# tiny_rack_v2_psu_exp_170.net
KiCad netlist of a schematic drawn in EAGLE
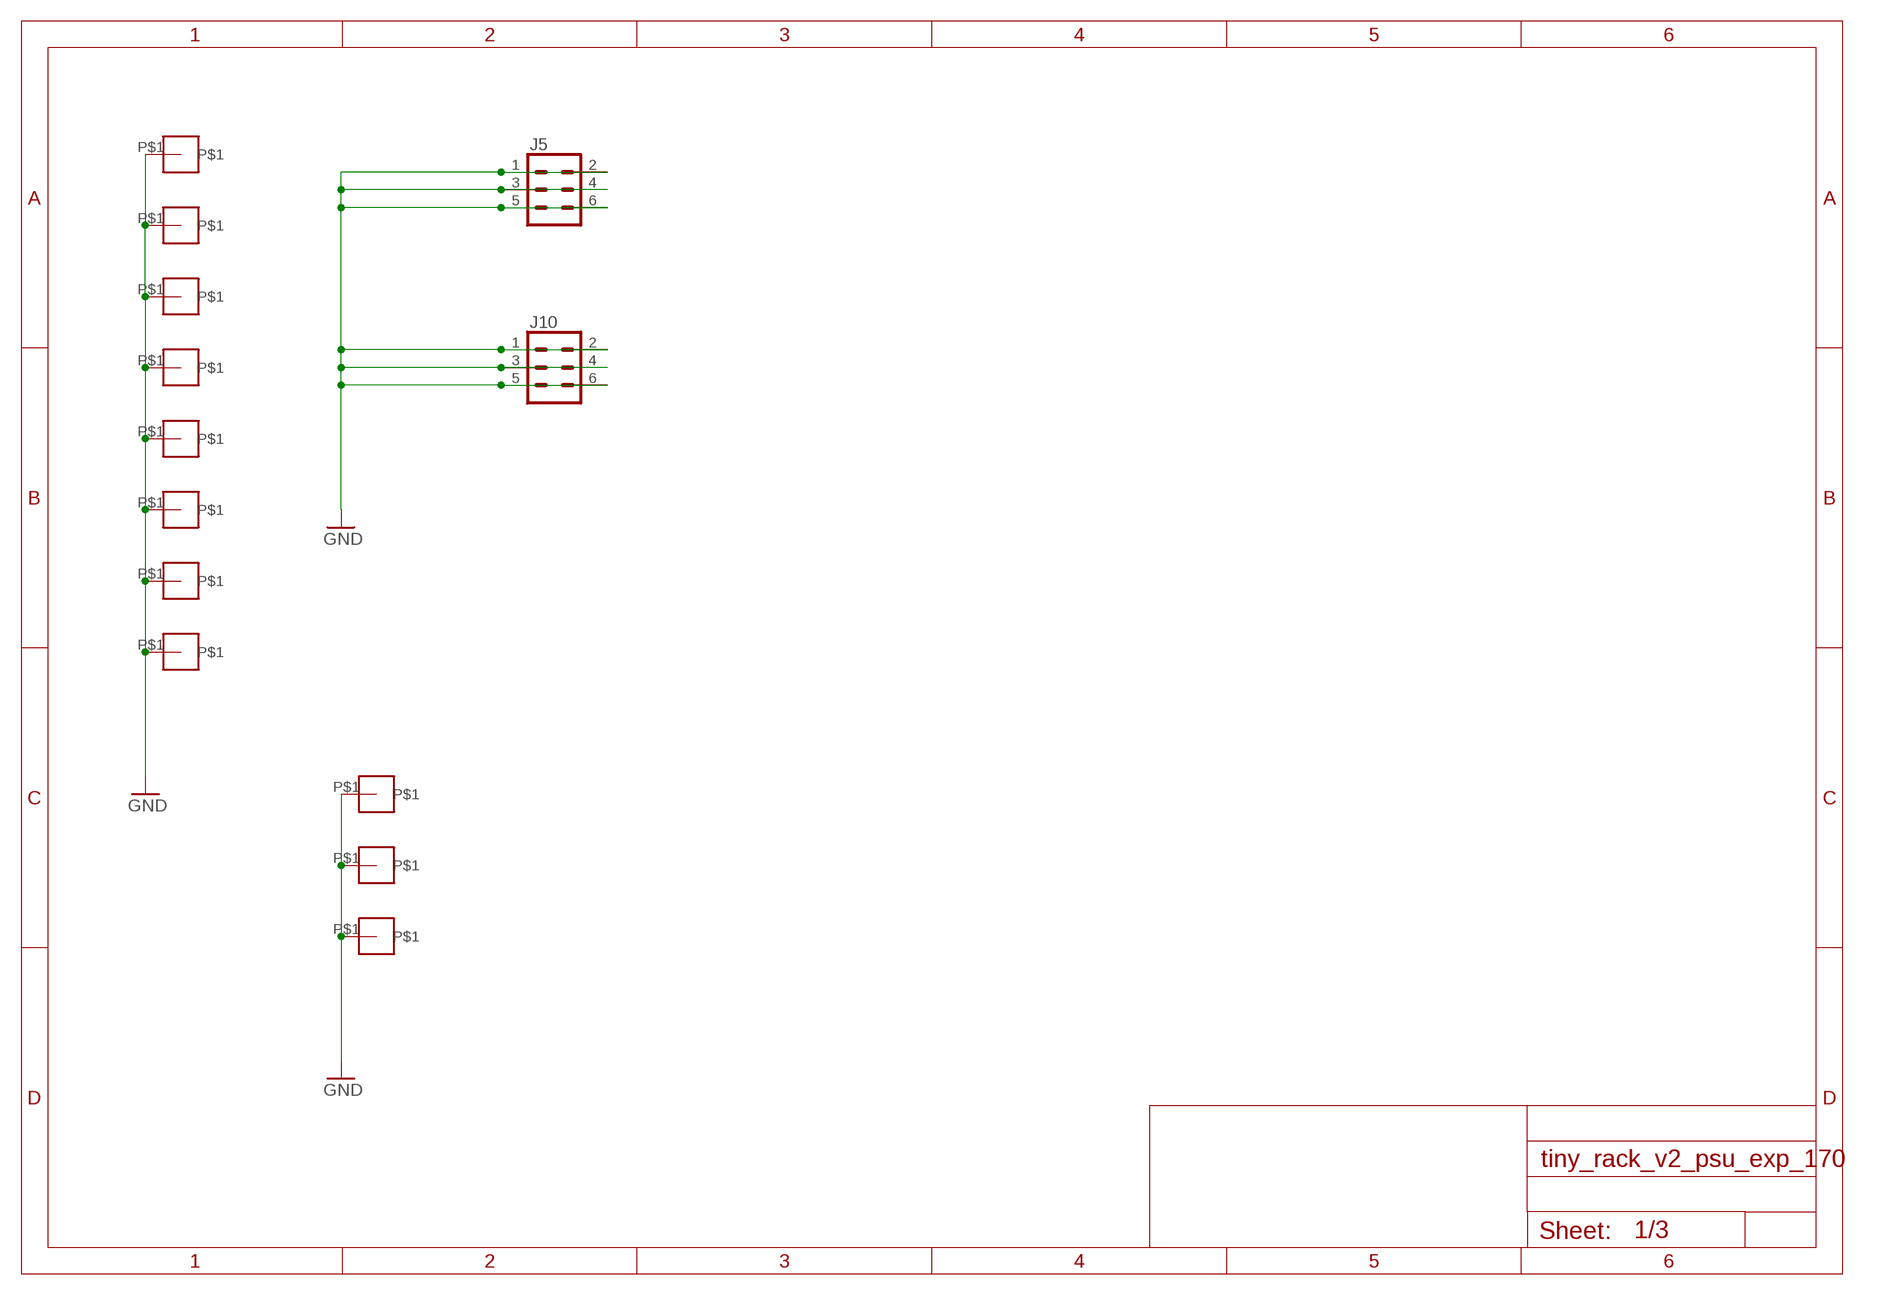
[diagram p0: schematic, sheet 1]
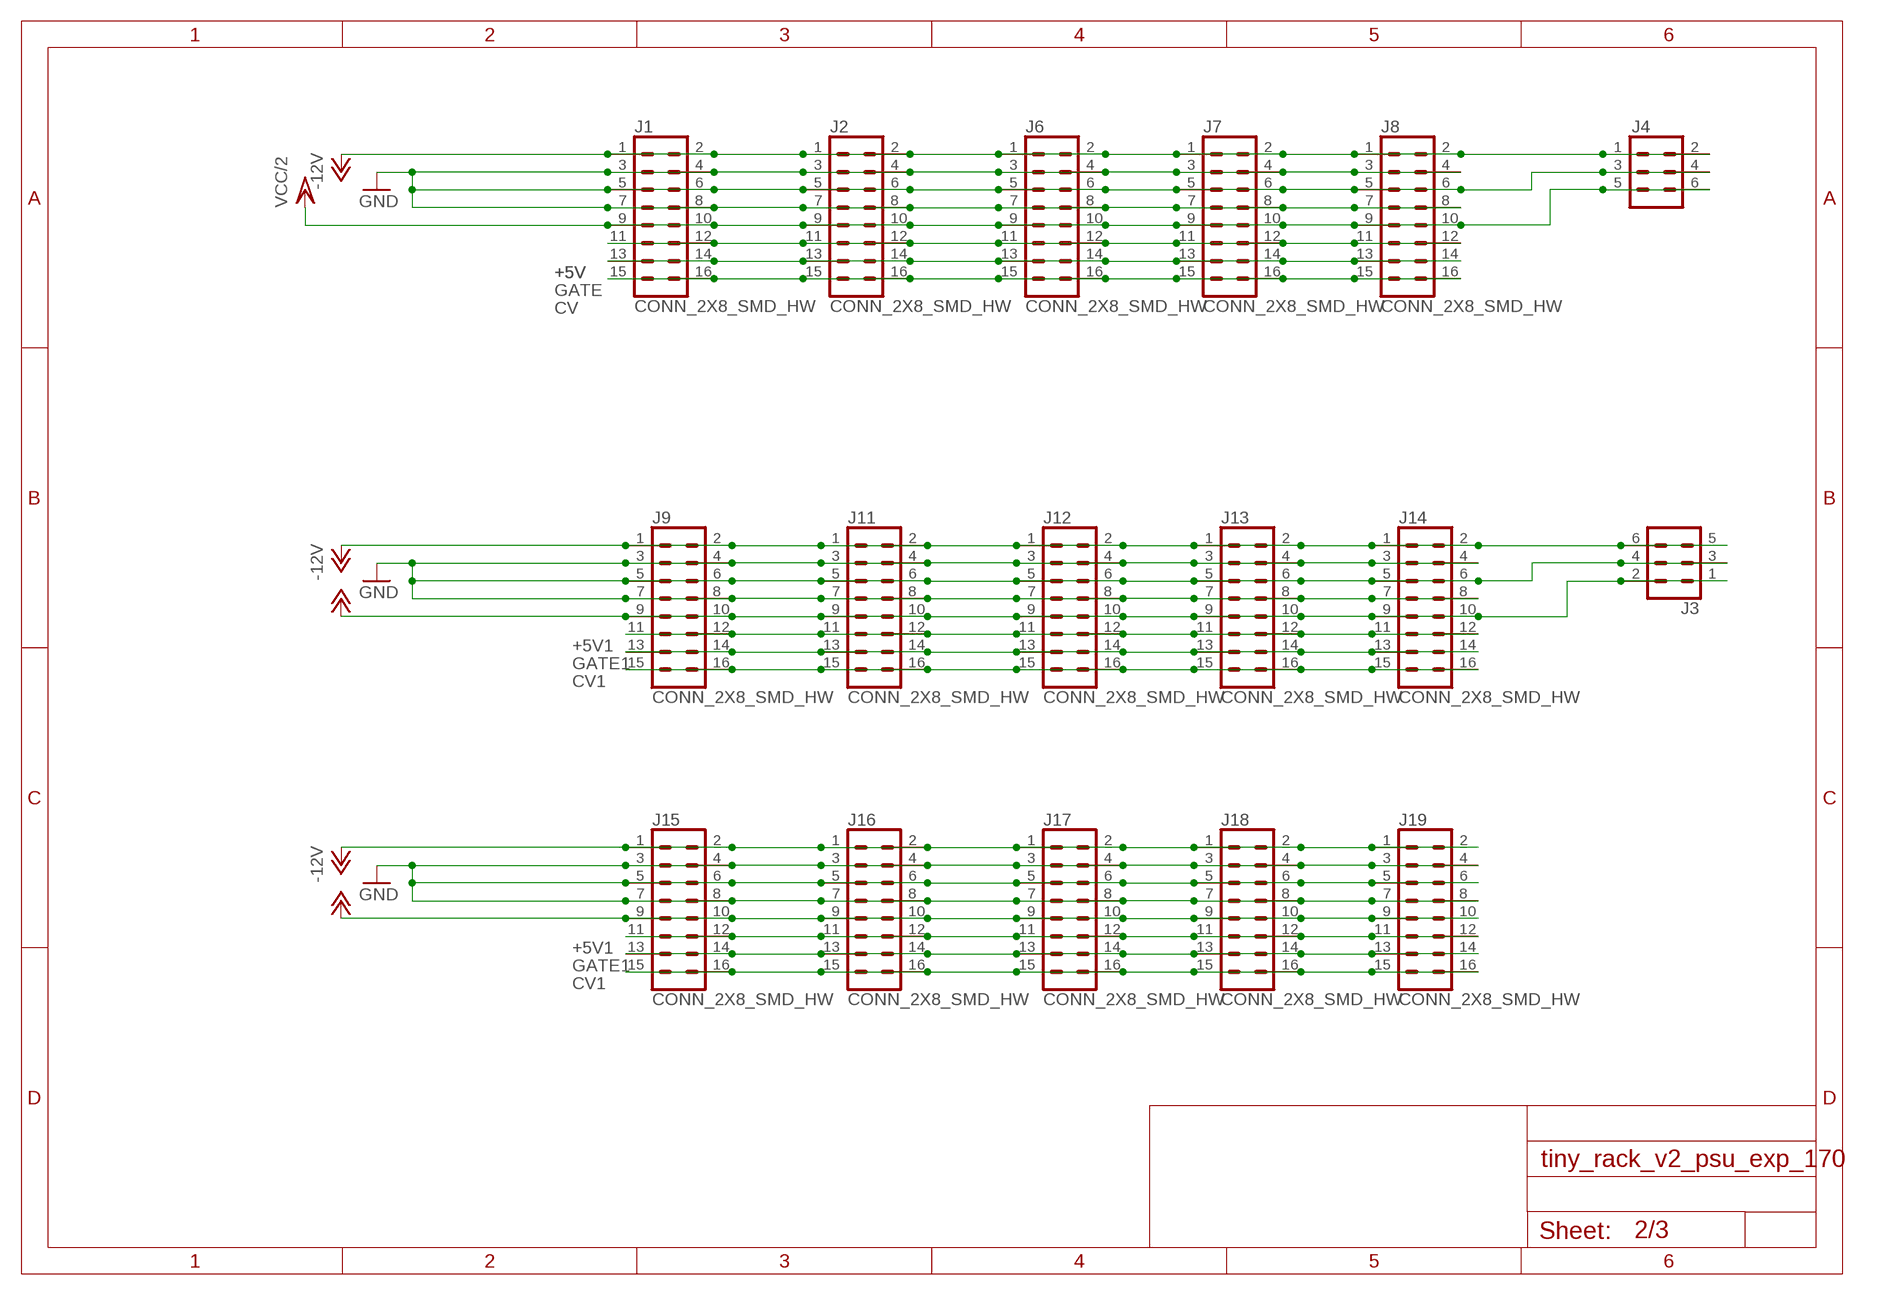
[diagram p1: schematic, sheet 2]
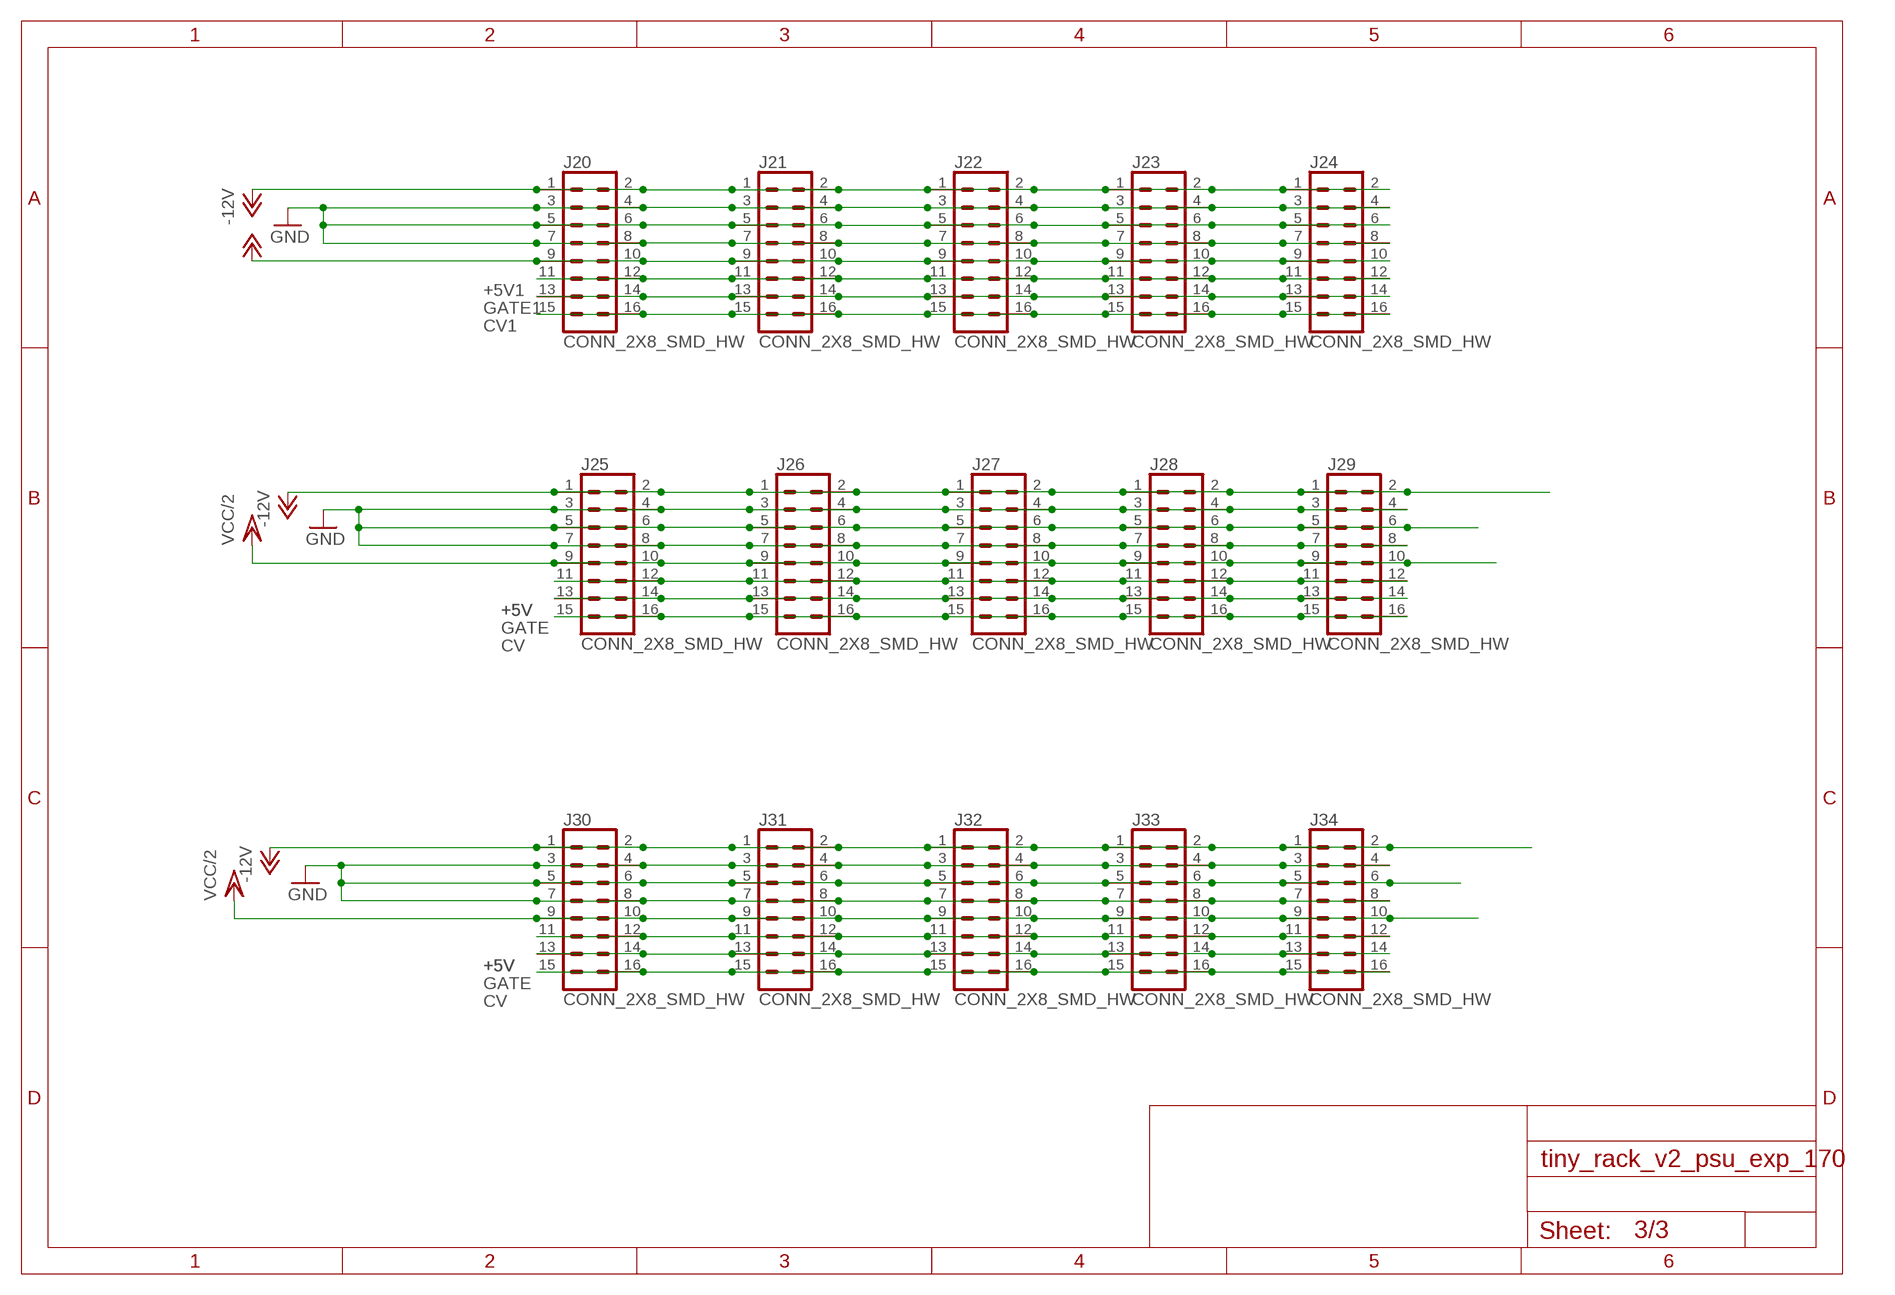
[diagram p2: schematic, sheet 3]

(export (version "E")
  (design (tool "Eeschema 10.0.6"))
  (components
    (comp (ref "J5")
      (value "CONN_03X2FEMALE_SMD")
      (footprint "eagle-import:2X3_SMD")
      (libsource (lib "eagle-import") (part "CONN_03X2FEMALE_SMD"))
    )
    (comp (ref "J10")
      (value "CONN_03X2FEMALE_SMD")
      (footprint "eagle-import:2X3_SMD")
      (libsource (lib "eagle-import") (part "CONN_03X2FEMALE_SMD"))
    )
    (comp (ref "U$1")
      (value "M3-HOLE")
      (footprint "eagle-import:M3-HOLE")
      (libsource (lib "eagle-import") (part "M3-HOLE"))
    )
    (comp (ref "U$2")
      (value "M3-HOLE")
      (footprint "eagle-import:M3-HOLE")
      (libsource (lib "eagle-import") (part "M3-HOLE"))
    )
    (comp (ref "U$3")
      (value "M3-HOLE")
      (footprint "eagle-import:M3-HOLE")
      (libsource (lib "eagle-import") (part "M3-HOLE"))
    )
    (comp (ref "U$4")
      (value "M3-HOLE")
      (footprint "eagle-import:M3-HOLE")
      (libsource (lib "eagle-import") (part "M3-HOLE"))
    )
    (comp (ref "U$5")
      (value "M3-HOLE")
      (footprint "eagle-import:M3-HOLE")
      (libsource (lib "eagle-import") (part "M3-HOLE"))
    )
    (comp (ref "U$6")
      (value "M3-HOLE")
      (footprint "eagle-import:M3-HOLE")
      (libsource (lib "eagle-import") (part "M3-HOLE"))
    )
    (comp (ref "U$8")
      (value "M3-HOLE")
      (footprint "eagle-import:M3-HOLE")
      (libsource (lib "eagle-import") (part "M3-HOLE"))
    )
    (comp (ref "U$9")
      (value "M3-HOLE")
      (footprint "eagle-import:M3-HOLE")
      (libsource (lib "eagle-import") (part "M3-HOLE"))
    )
    (comp (ref "U$10")
      (value "M3-HOLE")
      (footprint "eagle-import:M3-HOLE")
      (libsource (lib "eagle-import") (part "M3-HOLE"))
    )
    (comp (ref "U$11")
      (value "M3-HOLE")
      (footprint "eagle-import:M3-HOLE")
      (libsource (lib "eagle-import") (part "M3-HOLE"))
    )
    (comp (ref "U$12")
      (value "M3-HOLE")
      (footprint "eagle-import:M3-HOLE")
      (libsource (lib "eagle-import") (part "M3-HOLE"))
    )
    (comp (ref "J20")
      (value "CONN_2X8_SMD_HW")
      (footprint "eagle-import:2X8-SHROUDED_SMD_HW")
      (libsource (lib "eagle-import") (part "CONN_2X8_SMD_HW"))
    )
    (comp (ref "J21")
      (value "CONN_2X8_SMD_HW")
      (footprint "eagle-import:2X8-SHROUDED_SMD_HW")
      (libsource (lib "eagle-import") (part "CONN_2X8_SMD_HW"))
    )
    (comp (ref "J22")
      (value "CONN_2X8_SMD_HW")
      (footprint "eagle-import:2X8-SHROUDED_SMD_HW")
      (libsource (lib "eagle-import") (part "CONN_2X8_SMD_HW"))
    )
    (comp (ref "J23")
      (value "CONN_2X8_SMD_HW")
      (footprint "eagle-import:2X8-SHROUDED_SMD_HW")
      (libsource (lib "eagle-import") (part "CONN_2X8_SMD_HW"))
    )
    (comp (ref "J24")
      (value "CONN_2X8_SMD_HW")
      (footprint "eagle-import:2X8-SHROUDED_SMD_HW")
      (libsource (lib "eagle-import") (part "CONN_2X8_SMD_HW"))
    )
    (comp (ref "J25")
      (value "CONN_2X8_SMD_HW")
      (footprint "eagle-import:2X8-SHROUDED_SMD_HW")
      (libsource (lib "eagle-import") (part "CONN_2X8_SMD_HW"))
    )
    (comp (ref "J26")
      (value "CONN_2X8_SMD_HW")
      (footprint "eagle-import:2X8-SHROUDED_SMD_HW")
      (libsource (lib "eagle-import") (part "CONN_2X8_SMD_HW"))
    )
    (comp (ref "J27")
      (value "CONN_2X8_SMD_HW")
      (footprint "eagle-import:2X8-SHROUDED_SMD_HW")
      (libsource (lib "eagle-import") (part "CONN_2X8_SMD_HW"))
    )
    (comp (ref "J28")
      (value "CONN_2X8_SMD_HW")
      (footprint "eagle-import:2X8-SHROUDED_SMD_HW")
      (libsource (lib "eagle-import") (part "CONN_2X8_SMD_HW"))
    )
    (comp (ref "J29")
      (value "CONN_2X8_SMD_HW")
      (footprint "eagle-import:2X8-SHROUDED_SMD_HW")
      (libsource (lib "eagle-import") (part "CONN_2X8_SMD_HW"))
    )
    (comp (ref "J30")
      (value "CONN_2X8_SMD_HW")
      (footprint "eagle-import:2X8-SHROUDED_SMD_HW")
      (libsource (lib "eagle-import") (part "CONN_2X8_SMD_HW"))
    )
    (comp (ref "J31")
      (value "CONN_2X8_SMD_HW")
      (footprint "eagle-import:2X8-SHROUDED_SMD_HW")
      (libsource (lib "eagle-import") (part "CONN_2X8_SMD_HW"))
    )
    (comp (ref "J32")
      (value "CONN_2X8_SMD_HW")
      (footprint "eagle-import:2X8-SHROUDED_SMD_HW")
      (libsource (lib "eagle-import") (part "CONN_2X8_SMD_HW"))
    )
    (comp (ref "J33")
      (value "CONN_2X8_SMD_HW")
      (footprint "eagle-import:2X8-SHROUDED_SMD_HW")
      (libsource (lib "eagle-import") (part "CONN_2X8_SMD_HW"))
    )
    (comp (ref "J34")
      (value "CONN_2X8_SMD_HW")
      (footprint "eagle-import:2X8-SHROUDED_SMD_HW")
      (libsource (lib "eagle-import") (part "CONN_2X8_SMD_HW"))
    )
    (comp (ref "J1")
      (value "CONN_2X8_SMD_HW")
      (footprint "eagle-import:2X8-SHROUDED_SMD_HW")
      (libsource (lib "eagle-import") (part "CONN_2X8_SMD_HW"))
    )
    (comp (ref "J2")
      (value "CONN_2X8_SMD_HW")
      (footprint "eagle-import:2X8-SHROUDED_SMD_HW")
      (libsource (lib "eagle-import") (part "CONN_2X8_SMD_HW"))
    )
    (comp (ref "J3")
      (value "CONN_03X2FEMALE_SMD")
      (footprint "eagle-import:2X3_SMD")
      (libsource (lib "eagle-import") (part "CONN_03X2FEMALE_SMD"))
    )
    (comp (ref "J4")
      (value "CONN_03X2FEMALE_SMD")
      (footprint "eagle-import:2X3_SMD")
      (libsource (lib "eagle-import") (part "CONN_03X2FEMALE_SMD"))
    )
    (comp (ref "J6")
      (value "CONN_2X8_SMD_HW")
      (footprint "eagle-import:2X8-SHROUDED_SMD_HW")
      (libsource (lib "eagle-import") (part "CONN_2X8_SMD_HW"))
    )
    (comp (ref "J7")
      (value "CONN_2X8_SMD_HW")
      (footprint "eagle-import:2X8-SHROUDED_SMD_HW")
      (libsource (lib "eagle-import") (part "CONN_2X8_SMD_HW"))
    )
    (comp (ref "J8")
      (value "CONN_2X8_SMD_HW")
      (footprint "eagle-import:2X8-SHROUDED_SMD_HW")
      (libsource (lib "eagle-import") (part "CONN_2X8_SMD_HW"))
    )
    (comp (ref "J9")
      (value "CONN_2X8_SMD_HW")
      (footprint "eagle-import:2X8-SHROUDED_SMD_HW")
      (libsource (lib "eagle-import") (part "CONN_2X8_SMD_HW"))
    )
    (comp (ref "J11")
      (value "CONN_2X8_SMD_HW")
      (footprint "eagle-import:2X8-SHROUDED_SMD_HW")
      (libsource (lib "eagle-import") (part "CONN_2X8_SMD_HW"))
    )
    (comp (ref "J12")
      (value "CONN_2X8_SMD_HW")
      (footprint "eagle-import:2X8-SHROUDED_SMD_HW")
      (libsource (lib "eagle-import") (part "CONN_2X8_SMD_HW"))
    )
    (comp (ref "J13")
      (value "CONN_2X8_SMD_HW")
      (footprint "eagle-import:2X8-SHROUDED_SMD_HW")
      (libsource (lib "eagle-import") (part "CONN_2X8_SMD_HW"))
    )
    (comp (ref "J14")
      (value "CONN_2X8_SMD_HW")
      (footprint "eagle-import:2X8-SHROUDED_SMD_HW")
      (libsource (lib "eagle-import") (part "CONN_2X8_SMD_HW"))
    )
    (comp (ref "J15")
      (value "CONN_2X8_SMD_HW")
      (footprint "eagle-import:2X8-SHROUDED_SMD_HW")
      (libsource (lib "eagle-import") (part "CONN_2X8_SMD_HW"))
    )
    (comp (ref "J16")
      (value "CONN_2X8_SMD_HW")
      (footprint "eagle-import:2X8-SHROUDED_SMD_HW")
      (libsource (lib "eagle-import") (part "CONN_2X8_SMD_HW"))
    )
    (comp (ref "J17")
      (value "CONN_2X8_SMD_HW")
      (footprint "eagle-import:2X8-SHROUDED_SMD_HW")
      (libsource (lib "eagle-import") (part "CONN_2X8_SMD_HW"))
    )
    (comp (ref "J18")
      (value "CONN_2X8_SMD_HW")
      (footprint "eagle-import:2X8-SHROUDED_SMD_HW")
      (libsource (lib "eagle-import") (part "CONN_2X8_SMD_HW"))
    )
    (comp (ref "J19")
      (value "CONN_2X8_SMD_HW")
      (footprint "eagle-import:2X8-SHROUDED_SMD_HW")
      (libsource (lib "eagle-import") (part "CONN_2X8_SMD_HW"))
    )
  )
  (nets
    (net (code "1") (name "+5V") (class "Default")
      (node (ref "J1") (pin "11") (pinfunction "11_11") (pintype "passive"))
      (node (ref "J1") (pin "12") (pinfunction "12_12") (pintype "passive"))
      (node (ref "J2") (pin "11") (pinfunction "11_11") (pintype "passive"))
      (node (ref "J2") (pin "12") (pinfunction "12_12") (pintype "passive"))
      (node (ref "J25") (pin "11") (pinfunction "11_11") (pintype "passive"))
      (node (ref "J25") (pin "12") (pinfunction "12_12") (pintype "passive"))
      (node (ref "J26") (pin "11") (pinfunction "11_11") (pintype "passive"))
      (node (ref "J26") (pin "12") (pinfunction "12_12") (pintype "passive"))
      (node (ref "J27") (pin "11") (pinfunction "11_11") (pintype "passive"))
      (node (ref "J27") (pin "12") (pinfunction "12_12") (pintype "passive"))
      (node (ref "J28") (pin "11") (pinfunction "11_11") (pintype "passive"))
      (node (ref "J28") (pin "12") (pinfunction "12_12") (pintype "passive"))
      (node (ref "J29") (pin "11") (pinfunction "11_11") (pintype "passive"))
      (node (ref "J29") (pin "12") (pinfunction "12_12") (pintype "passive"))
      (node (ref "J30") (pin "11") (pinfunction "11_11") (pintype "passive"))
      (node (ref "J30") (pin "12") (pinfunction "12_12") (pintype "passive"))
      (node (ref "J31") (pin "11") (pinfunction "11_11") (pintype "passive"))
      (node (ref "J31") (pin "12") (pinfunction "12_12") (pintype "passive"))
      (node (ref "J32") (pin "11") (pinfunction "11_11") (pintype "passive"))
      (node (ref "J32") (pin "12") (pinfunction "12_12") (pintype "passive"))
      (node (ref "J33") (pin "11") (pinfunction "11_11") (pintype "passive"))
      (node (ref "J33") (pin "12") (pinfunction "12_12") (pintype "passive"))
      (node (ref "J34") (pin "11") (pinfunction "11_11") (pintype "passive"))
      (node (ref "J34") (pin "12") (pinfunction "12_12") (pintype "passive"))
      (node (ref "J6") (pin "11") (pinfunction "11_11") (pintype "passive"))
      (node (ref "J6") (pin "12") (pinfunction "12_12") (pintype "passive"))
      (node (ref "J7") (pin "11") (pinfunction "11_11") (pintype "passive"))
      (node (ref "J7") (pin "12") (pinfunction "12_12") (pintype "passive"))
      (node (ref "J8") (pin "11") (pinfunction "11_11") (pintype "passive"))
      (node (ref "J8") (pin "12") (pinfunction "12_12") (pintype "passive"))
    )
    (net (code "2") (name "+5V1") (class "Default")
      (node (ref "J11") (pin "11") (pinfunction "11_11") (pintype "passive"))
      (node (ref "J11") (pin "12") (pinfunction "12_12") (pintype "passive"))
      (node (ref "J12") (pin "11") (pinfunction "11_11") (pintype "passive"))
      (node (ref "J12") (pin "12") (pinfunction "12_12") (pintype "passive"))
      (node (ref "J13") (pin "11") (pinfunction "11_11") (pintype "passive"))
      (node (ref "J13") (pin "12") (pinfunction "12_12") (pintype "passive"))
      (node (ref "J14") (pin "11") (pinfunction "11_11") (pintype "passive"))
      (node (ref "J14") (pin "12") (pinfunction "12_12") (pintype "passive"))
      (node (ref "J15") (pin "11") (pinfunction "11_11") (pintype "passive"))
      (node (ref "J15") (pin "12") (pinfunction "12_12") (pintype "passive"))
      (node (ref "J16") (pin "11") (pinfunction "11_11") (pintype "passive"))
      (node (ref "J16") (pin "12") (pinfunction "12_12") (pintype "passive"))
      (node (ref "J17") (pin "11") (pinfunction "11_11") (pintype "passive"))
      (node (ref "J17") (pin "12") (pinfunction "12_12") (pintype "passive"))
      (node (ref "J18") (pin "11") (pinfunction "11_11") (pintype "passive"))
      (node (ref "J18") (pin "12") (pinfunction "12_12") (pintype "passive"))
      (node (ref "J19") (pin "11") (pinfunction "11_11") (pintype "passive"))
      (node (ref "J19") (pin "12") (pinfunction "12_12") (pintype "passive"))
      (node (ref "J20") (pin "11") (pinfunction "11_11") (pintype "passive"))
      (node (ref "J20") (pin "12") (pinfunction "12_12") (pintype "passive"))
      (node (ref "J21") (pin "11") (pinfunction "11_11") (pintype "passive"))
      (node (ref "J21") (pin "12") (pinfunction "12_12") (pintype "passive"))
      (node (ref "J22") (pin "11") (pinfunction "11_11") (pintype "passive"))
      (node (ref "J22") (pin "12") (pinfunction "12_12") (pintype "passive"))
      (node (ref "J23") (pin "11") (pinfunction "11_11") (pintype "passive"))
      (node (ref "J23") (pin "12") (pinfunction "12_12") (pintype "passive"))
      (node (ref "J24") (pin "11") (pinfunction "11_11") (pintype "passive"))
      (node (ref "J24") (pin "12") (pinfunction "12_12") (pintype "passive"))
      (node (ref "J9") (pin "11") (pinfunction "11_11") (pintype "passive"))
      (node (ref "J9") (pin "12") (pinfunction "12_12") (pintype "passive"))
    )
    (net (code "3") (name "+12V") (class "Default")
      (node (ref "J11") (pin "10") (pinfunction "10_10") (pintype "passive"))
      (node (ref "J11") (pin "9") (pinfunction "9_9") (pintype "passive"))
      (node (ref "J12") (pin "10") (pinfunction "10_10") (pintype "passive"))
      (node (ref "J12") (pin "9") (pinfunction "9_9") (pintype "passive"))
      (node (ref "J13") (pin "10") (pinfunction "10_10") (pintype "passive"))
      (node (ref "J13") (pin "9") (pinfunction "9_9") (pintype "passive"))
      (node (ref "J14") (pin "10") (pinfunction "10_10") (pintype "passive"))
      (node (ref "J14") (pin "9") (pinfunction "9_9") (pintype "passive"))
      (node (ref "J15") (pin "10") (pinfunction "10_10") (pintype "passive"))
      (node (ref "J15") (pin "9") (pinfunction "9_9") (pintype "passive"))
      (node (ref "J16") (pin "10") (pinfunction "10_10") (pintype "passive"))
      (node (ref "J16") (pin "9") (pinfunction "9_9") (pintype "passive"))
      (node (ref "J17") (pin "10") (pinfunction "10_10") (pintype "passive"))
      (node (ref "J17") (pin "9") (pinfunction "9_9") (pintype "passive"))
      (node (ref "J18") (pin "10") (pinfunction "10_10") (pintype "passive"))
      (node (ref "J18") (pin "9") (pinfunction "9_9") (pintype "passive"))
      (node (ref "J19") (pin "10") (pinfunction "10_10") (pintype "passive"))
      (node (ref "J19") (pin "9") (pinfunction "9_9") (pintype "passive"))
      (node (ref "J20") (pin "10") (pinfunction "10_10") (pintype "passive"))
      (node (ref "J20") (pin "9") (pinfunction "9_9") (pintype "passive"))
      (node (ref "J21") (pin "10") (pinfunction "10_10") (pintype "passive"))
      (node (ref "J21") (pin "9") (pinfunction "9_9") (pintype "passive"))
      (node (ref "J22") (pin "10") (pinfunction "10_10") (pintype "passive"))
      (node (ref "J22") (pin "9") (pinfunction "9_9") (pintype "passive"))
      (node (ref "J23") (pin "10") (pinfunction "10_10") (pintype "passive"))
      (node (ref "J23") (pin "9") (pinfunction "9_9") (pintype "passive"))
      (node (ref "J24") (pin "10") (pinfunction "10_10") (pintype "passive"))
      (node (ref "J24") (pin "9") (pinfunction "9_9") (pintype "passive"))
      (node (ref "J3") (pin "1") (pinfunction "1_1") (pintype "bidirectional"))
      (node (ref "J3") (pin "2") (pinfunction "2_2") (pintype "bidirectional"))
      (node (ref "J9") (pin "10") (pinfunction "10_10") (pintype "passive"))
      (node (ref "J9") (pin "9") (pinfunction "9_9") (pintype "passive"))
    )
    (net (code "4") (name "-12V") (class "Default")
      (node (ref "J1") (pin "1") (pinfunction "1_1") (pintype "passive"))
      (node (ref "J1") (pin "2") (pinfunction "2_2") (pintype "passive"))
      (node (ref "J11") (pin "1") (pinfunction "1_1") (pintype "passive"))
      (node (ref "J11") (pin "2") (pinfunction "2_2") (pintype "passive"))
      (node (ref "J12") (pin "1") (pinfunction "1_1") (pintype "passive"))
      (node (ref "J12") (pin "2") (pinfunction "2_2") (pintype "passive"))
      (node (ref "J13") (pin "1") (pinfunction "1_1") (pintype "passive"))
      (node (ref "J13") (pin "2") (pinfunction "2_2") (pintype "passive"))
      (node (ref "J14") (pin "1") (pinfunction "1_1") (pintype "passive"))
      (node (ref "J14") (pin "2") (pinfunction "2_2") (pintype "passive"))
      (node (ref "J15") (pin "1") (pinfunction "1_1") (pintype "passive"))
      (node (ref "J15") (pin "2") (pinfunction "2_2") (pintype "passive"))
      (node (ref "J16") (pin "1") (pinfunction "1_1") (pintype "passive"))
      (node (ref "J16") (pin "2") (pinfunction "2_2") (pintype "passive"))
      (node (ref "J17") (pin "1") (pinfunction "1_1") (pintype "passive"))
      (node (ref "J17") (pin "2") (pinfunction "2_2") (pintype "passive"))
      (node (ref "J18") (pin "1") (pinfunction "1_1") (pintype "passive"))
      (node (ref "J18") (pin "2") (pinfunction "2_2") (pintype "passive"))
      (node (ref "J19") (pin "1") (pinfunction "1_1") (pintype "passive"))
      (node (ref "J19") (pin "2") (pinfunction "2_2") (pintype "passive"))
      (node (ref "J2") (pin "1") (pinfunction "1_1") (pintype "passive"))
      (node (ref "J2") (pin "2") (pinfunction "2_2") (pintype "passive"))
      (node (ref "J20") (pin "1") (pinfunction "1_1") (pintype "passive"))
      (node (ref "J20") (pin "2") (pinfunction "2_2") (pintype "passive"))
      (node (ref "J21") (pin "1") (pinfunction "1_1") (pintype "passive"))
      (node (ref "J21") (pin "2") (pinfunction "2_2") (pintype "passive"))
      (node (ref "J22") (pin "1") (pinfunction "1_1") (pintype "passive"))
      (node (ref "J22") (pin "2") (pinfunction "2_2") (pintype "passive"))
      (node (ref "J23") (pin "1") (pinfunction "1_1") (pintype "passive"))
      (node (ref "J23") (pin "2") (pinfunction "2_2") (pintype "passive"))
      (node (ref "J24") (pin "1") (pinfunction "1_1") (pintype "passive"))
      (node (ref "J24") (pin "2") (pinfunction "2_2") (pintype "passive"))
      (node (ref "J25") (pin "1") (pinfunction "1_1") (pintype "passive"))
      (node (ref "J25") (pin "2") (pinfunction "2_2") (pintype "passive"))
      (node (ref "J26") (pin "1") (pinfunction "1_1") (pintype "passive"))
      (node (ref "J26") (pin "2") (pinfunction "2_2") (pintype "passive"))
      (node (ref "J27") (pin "1") (pinfunction "1_1") (pintype "passive"))
      (node (ref "J27") (pin "2") (pinfunction "2_2") (pintype "passive"))
      (node (ref "J28") (pin "1") (pinfunction "1_1") (pintype "passive"))
      (node (ref "J28") (pin "2") (pinfunction "2_2") (pintype "passive"))
      (node (ref "J29") (pin "1") (pinfunction "1_1") (pintype "passive"))
      (node (ref "J29") (pin "2") (pinfunction "2_2") (pintype "passive"))
      (node (ref "J3") (pin "5") (pinfunction "5_5") (pintype "bidirectional"))
      (node (ref "J3") (pin "6") (pinfunction "6_6") (pintype "bidirectional"))
      (node (ref "J30") (pin "1") (pinfunction "1_1") (pintype "passive"))
      (node (ref "J30") (pin "2") (pinfunction "2_2") (pintype "passive"))
      (node (ref "J31") (pin "1") (pinfunction "1_1") (pintype "passive"))
      (node (ref "J31") (pin "2") (pinfunction "2_2") (pintype "passive"))
      (node (ref "J32") (pin "1") (pinfunction "1_1") (pintype "passive"))
      (node (ref "J32") (pin "2") (pinfunction "2_2") (pintype "passive"))
      (node (ref "J33") (pin "1") (pinfunction "1_1") (pintype "passive"))
      (node (ref "J33") (pin "2") (pinfunction "2_2") (pintype "passive"))
      (node (ref "J34") (pin "1") (pinfunction "1_1") (pintype "passive"))
      (node (ref "J34") (pin "2") (pinfunction "2_2") (pintype "passive"))
      (node (ref "J4") (pin "1") (pinfunction "1_1") (pintype "bidirectional"))
      (node (ref "J4") (pin "2") (pinfunction "2_2") (pintype "bidirectional"))
      (node (ref "J6") (pin "1") (pinfunction "1_1") (pintype "passive"))
      (node (ref "J6") (pin "2") (pinfunction "2_2") (pintype "passive"))
      (node (ref "J7") (pin "1") (pinfunction "1_1") (pintype "passive"))
      (node (ref "J7") (pin "2") (pinfunction "2_2") (pintype "passive"))
      (node (ref "J8") (pin "1") (pinfunction "1_1") (pintype "passive"))
      (node (ref "J8") (pin "2") (pinfunction "2_2") (pintype "passive"))
      (node (ref "J9") (pin "1") (pinfunction "1_1") (pintype "passive"))
      (node (ref "J9") (pin "2") (pinfunction "2_2") (pintype "passive"))
    )
    (net (code "5") (name "CV") (class "Default")
      (node (ref "J1") (pin "15") (pinfunction "15_15") (pintype "passive"))
      (node (ref "J1") (pin "16") (pinfunction "16_16") (pintype "passive"))
      (node (ref "J2") (pin "15") (pinfunction "15_15") (pintype "passive"))
      (node (ref "J2") (pin "16") (pinfunction "16_16") (pintype "passive"))
      (node (ref "J25") (pin "15") (pinfunction "15_15") (pintype "passive"))
      (node (ref "J25") (pin "16") (pinfunction "16_16") (pintype "passive"))
      (node (ref "J26") (pin "15") (pinfunction "15_15") (pintype "passive"))
      (node (ref "J26") (pin "16") (pinfunction "16_16") (pintype "passive"))
      (node (ref "J27") (pin "15") (pinfunction "15_15") (pintype "passive"))
      (node (ref "J27") (pin "16") (pinfunction "16_16") (pintype "passive"))
      (node (ref "J28") (pin "15") (pinfunction "15_15") (pintype "passive"))
      (node (ref "J28") (pin "16") (pinfunction "16_16") (pintype "passive"))
      (node (ref "J29") (pin "15") (pinfunction "15_15") (pintype "passive"))
      (node (ref "J29") (pin "16") (pinfunction "16_16") (pintype "passive"))
      (node (ref "J30") (pin "15") (pinfunction "15_15") (pintype "passive"))
      (node (ref "J30") (pin "16") (pinfunction "16_16") (pintype "passive"))
      (node (ref "J31") (pin "15") (pinfunction "15_15") (pintype "passive"))
      (node (ref "J31") (pin "16") (pinfunction "16_16") (pintype "passive"))
      (node (ref "J32") (pin "15") (pinfunction "15_15") (pintype "passive"))
      (node (ref "J32") (pin "16") (pinfunction "16_16") (pintype "passive"))
      (node (ref "J33") (pin "15") (pinfunction "15_15") (pintype "passive"))
      (node (ref "J33") (pin "16") (pinfunction "16_16") (pintype "passive"))
      (node (ref "J34") (pin "15") (pinfunction "15_15") (pintype "passive"))
      (node (ref "J34") (pin "16") (pinfunction "16_16") (pintype "passive"))
      (node (ref "J6") (pin "15") (pinfunction "15_15") (pintype "passive"))
      (node (ref "J6") (pin "16") (pinfunction "16_16") (pintype "passive"))
      (node (ref "J7") (pin "15") (pinfunction "15_15") (pintype "passive"))
      (node (ref "J7") (pin "16") (pinfunction "16_16") (pintype "passive"))
      (node (ref "J8") (pin "15") (pinfunction "15_15") (pintype "passive"))
      (node (ref "J8") (pin "16") (pinfunction "16_16") (pintype "passive"))
    )
    (net (code "6") (name "CV1") (class "Default")
      (node (ref "J11") (pin "15") (pinfunction "15_15") (pintype "passive"))
      (node (ref "J11") (pin "16") (pinfunction "16_16") (pintype "passive"))
      (node (ref "J12") (pin "15") (pinfunction "15_15") (pintype "passive"))
      (node (ref "J12") (pin "16") (pinfunction "16_16") (pintype "passive"))
      (node (ref "J13") (pin "15") (pinfunction "15_15") (pintype "passive"))
      (node (ref "J13") (pin "16") (pinfunction "16_16") (pintype "passive"))
      (node (ref "J14") (pin "15") (pinfunction "15_15") (pintype "passive"))
      (node (ref "J14") (pin "16") (pinfunction "16_16") (pintype "passive"))
      (node (ref "J15") (pin "15") (pinfunction "15_15") (pintype "passive"))
      (node (ref "J15") (pin "16") (pinfunction "16_16") (pintype "passive"))
      (node (ref "J16") (pin "15") (pinfunction "15_15") (pintype "passive"))
      (node (ref "J16") (pin "16") (pinfunction "16_16") (pintype "passive"))
      (node (ref "J17") (pin "15") (pinfunction "15_15") (pintype "passive"))
      (node (ref "J17") (pin "16") (pinfunction "16_16") (pintype "passive"))
      (node (ref "J18") (pin "15") (pinfunction "15_15") (pintype "passive"))
      (node (ref "J18") (pin "16") (pinfunction "16_16") (pintype "passive"))
      (node (ref "J19") (pin "15") (pinfunction "15_15") (pintype "passive"))
      (node (ref "J19") (pin "16") (pinfunction "16_16") (pintype "passive"))
      (node (ref "J20") (pin "15") (pinfunction "15_15") (pintype "passive"))
      (node (ref "J20") (pin "16") (pinfunction "16_16") (pintype "passive"))
      (node (ref "J21") (pin "15") (pinfunction "15_15") (pintype "passive"))
      (node (ref "J21") (pin "16") (pinfunction "16_16") (pintype "passive"))
      (node (ref "J22") (pin "15") (pinfunction "15_15") (pintype "passive"))
      (node (ref "J22") (pin "16") (pinfunction "16_16") (pintype "passive"))
      (node (ref "J23") (pin "15") (pinfunction "15_15") (pintype "passive"))
      (node (ref "J23") (pin "16") (pinfunction "16_16") (pintype "passive"))
      (node (ref "J24") (pin "15") (pinfunction "15_15") (pintype "passive"))
      (node (ref "J24") (pin "16") (pinfunction "16_16") (pintype "passive"))
      (node (ref "J9") (pin "15") (pinfunction "15_15") (pintype "passive"))
      (node (ref "J9") (pin "16") (pinfunction "16_16") (pintype "passive"))
    )
    (net (code "7") (name "GATE") (class "Default")
      (node (ref "J1") (pin "13") (pinfunction "13_13") (pintype "passive"))
      (node (ref "J1") (pin "14") (pinfunction "14_14") (pintype "passive"))
      (node (ref "J2") (pin "13") (pinfunction "13_13") (pintype "passive"))
      (node (ref "J2") (pin "14") (pinfunction "14_14") (pintype "passive"))
      (node (ref "J25") (pin "13") (pinfunction "13_13") (pintype "passive"))
      (node (ref "J25") (pin "14") (pinfunction "14_14") (pintype "passive"))
      (node (ref "J26") (pin "13") (pinfunction "13_13") (pintype "passive"))
      (node (ref "J26") (pin "14") (pinfunction "14_14") (pintype "passive"))
      (node (ref "J27") (pin "13") (pinfunction "13_13") (pintype "passive"))
      (node (ref "J27") (pin "14") (pinfunction "14_14") (pintype "passive"))
      (node (ref "J28") (pin "13") (pinfunction "13_13") (pintype "passive"))
      (node (ref "J28") (pin "14") (pinfunction "14_14") (pintype "passive"))
      (node (ref "J29") (pin "13") (pinfunction "13_13") (pintype "passive"))
      (node (ref "J29") (pin "14") (pinfunction "14_14") (pintype "passive"))
      (node (ref "J30") (pin "13") (pinfunction "13_13") (pintype "passive"))
      (node (ref "J30") (pin "14") (pinfunction "14_14") (pintype "passive"))
      (node (ref "J31") (pin "13") (pinfunction "13_13") (pintype "passive"))
      (node (ref "J31") (pin "14") (pinfunction "14_14") (pintype "passive"))
      (node (ref "J32") (pin "13") (pinfunction "13_13") (pintype "passive"))
      (node (ref "J32") (pin "14") (pinfunction "14_14") (pintype "passive"))
      (node (ref "J33") (pin "13") (pinfunction "13_13") (pintype "passive"))
      (node (ref "J33") (pin "14") (pinfunction "14_14") (pintype "passive"))
      (node (ref "J34") (pin "13") (pinfunction "13_13") (pintype "passive"))
      (node (ref "J34") (pin "14") (pinfunction "14_14") (pintype "passive"))
      (node (ref "J6") (pin "13") (pinfunction "13_13") (pintype "passive"))
      (node (ref "J6") (pin "14") (pinfunction "14_14") (pintype "passive"))
      (node (ref "J7") (pin "13") (pinfunction "13_13") (pintype "passive"))
      (node (ref "J7") (pin "14") (pinfunction "14_14") (pintype "passive"))
      (node (ref "J8") (pin "13") (pinfunction "13_13") (pintype "passive"))
      (node (ref "J8") (pin "14") (pinfunction "14_14") (pintype "passive"))
    )
    (net (code "8") (name "GATE1") (class "Default")
      (node (ref "J11") (pin "13") (pinfunction "13_13") (pintype "passive"))
      (node (ref "J11") (pin "14") (pinfunction "14_14") (pintype "passive"))
      (node (ref "J12") (pin "13") (pinfunction "13_13") (pintype "passive"))
      (node (ref "J12") (pin "14") (pinfunction "14_14") (pintype "passive"))
      (node (ref "J13") (pin "13") (pinfunction "13_13") (pintype "passive"))
      (node (ref "J13") (pin "14") (pinfunction "14_14") (pintype "passive"))
      (node (ref "J14") (pin "13") (pinfunction "13_13") (pintype "passive"))
      (node (ref "J14") (pin "14") (pinfunction "14_14") (pintype "passive"))
      (node (ref "J15") (pin "13") (pinfunction "13_13") (pintype "passive"))
      (node (ref "J15") (pin "14") (pinfunction "14_14") (pintype "passive"))
      (node (ref "J16") (pin "13") (pinfunction "13_13") (pintype "passive"))
      (node (ref "J16") (pin "14") (pinfunction "14_14") (pintype "passive"))
      (node (ref "J17") (pin "13") (pinfunction "13_13") (pintype "passive"))
      (node (ref "J17") (pin "14") (pinfunction "14_14") (pintype "passive"))
      (node (ref "J18") (pin "13") (pinfunction "13_13") (pintype "passive"))
      (node (ref "J18") (pin "14") (pinfunction "14_14") (pintype "passive"))
      (node (ref "J19") (pin "13") (pinfunction "13_13") (pintype "passive"))
      (node (ref "J19") (pin "14") (pinfunction "14_14") (pintype "passive"))
      (node (ref "J20") (pin "13") (pinfunction "13_13") (pintype "passive"))
      (node (ref "J20") (pin "14") (pinfunction "14_14") (pintype "passive"))
      (node (ref "J21") (pin "13") (pinfunction "13_13") (pintype "passive"))
      (node (ref "J21") (pin "14") (pinfunction "14_14") (pintype "passive"))
      (node (ref "J22") (pin "13") (pinfunction "13_13") (pintype "passive"))
      (node (ref "J22") (pin "14") (pinfunction "14_14") (pintype "passive"))
      (node (ref "J23") (pin "13") (pinfunction "13_13") (pintype "passive"))
      (node (ref "J23") (pin "14") (pinfunction "14_14") (pintype "passive"))
      (node (ref "J24") (pin "13") (pinfunction "13_13") (pintype "passive"))
      (node (ref "J24") (pin "14") (pinfunction "14_14") (pintype "passive"))
      (node (ref "J9") (pin "13") (pinfunction "13_13") (pintype "passive"))
      (node (ref "J9") (pin "14") (pinfunction "14_14") (pintype "passive"))
    )
    (net (code "9") (name "GND") (class "Default")
      (node (ref "J1") (pin "3") (pinfunction "3_3") (pintype "passive"))
      (node (ref "J1") (pin "4") (pinfunction "4_4") (pintype "passive"))
      (node (ref "J1") (pin "5") (pinfunction "5_5") (pintype "passive"))
      (node (ref "J1") (pin "6") (pinfunction "6_6") (pintype "passive"))
      (node (ref "J1") (pin "7") (pinfunction "7_7") (pintype "passive"))
      (node (ref "J1") (pin "8") (pinfunction "8_8") (pintype "passive"))
      (node (ref "J10") (pin "1") (pinfunction "1_1") (pintype "bidirectional"))
      (node (ref "J10") (pin "2") (pinfunction "2_2") (pintype "bidirectional"))
      (node (ref "J10") (pin "3") (pinfunction "3_3") (pintype "bidirectional"))
      (node (ref "J10") (pin "4") (pinfunction "4_4") (pintype "bidirectional"))
      (node (ref "J10") (pin "5") (pinfunction "5_5") (pintype "bidirectional"))
      (node (ref "J10") (pin "6") (pinfunction "6_6") (pintype "bidirectional"))
      (node (ref "J11") (pin "3") (pinfunction "3_3") (pintype "passive"))
      (node (ref "J11") (pin "4") (pinfunction "4_4") (pintype "passive"))
      (node (ref "J11") (pin "5") (pinfunction "5_5") (pintype "passive"))
      (node (ref "J11") (pin "6") (pinfunction "6_6") (pintype "passive"))
      (node (ref "J11") (pin "7") (pinfunction "7_7") (pintype "passive"))
      (node (ref "J11") (pin "8") (pinfunction "8_8") (pintype "passive"))
      (node (ref "J12") (pin "3") (pinfunction "3_3") (pintype "passive"))
      (node (ref "J12") (pin "4") (pinfunction "4_4") (pintype "passive"))
      (node (ref "J12") (pin "5") (pinfunction "5_5") (pintype "passive"))
      (node (ref "J12") (pin "6") (pinfunction "6_6") (pintype "passive"))
      (node (ref "J12") (pin "7") (pinfunction "7_7") (pintype "passive"))
      (node (ref "J12") (pin "8") (pinfunction "8_8") (pintype "passive"))
      (node (ref "J13") (pin "3") (pinfunction "3_3") (pintype "passive"))
      (node (ref "J13") (pin "4") (pinfunction "4_4") (pintype "passive"))
      (node (ref "J13") (pin "5") (pinfunction "5_5") (pintype "passive"))
      (node (ref "J13") (pin "6") (pinfunction "6_6") (pintype "passive"))
      (node (ref "J13") (pin "7") (pinfunction "7_7") (pintype "passive"))
      (node (ref "J13") (pin "8") (pinfunction "8_8") (pintype "passive"))
      (node (ref "J14") (pin "3") (pinfunction "3_3") (pintype "passive"))
      (node (ref "J14") (pin "4") (pinfunction "4_4") (pintype "passive"))
      (node (ref "J14") (pin "5") (pinfunction "5_5") (pintype "passive"))
      (node (ref "J14") (pin "6") (pinfunction "6_6") (pintype "passive"))
      (node (ref "J14") (pin "7") (pinfunction "7_7") (pintype "passive"))
      (node (ref "J14") (pin "8") (pinfunction "8_8") (pintype "passive"))
      (node (ref "J15") (pin "3") (pinfunction "3_3") (pintype "passive"))
      (node (ref "J15") (pin "4") (pinfunction "4_4") (pintype "passive"))
      (node (ref "J15") (pin "5") (pinfunction "5_5") (pintype "passive"))
      (node (ref "J15") (pin "6") (pinfunction "6_6") (pintype "passive"))
      (node (ref "J15") (pin "7") (pinfunction "7_7") (pintype "passive"))
      (node (ref "J15") (pin "8") (pinfunction "8_8") (pintype "passive"))
      (node (ref "J16") (pin "3") (pinfunction "3_3") (pintype "passive"))
      (node (ref "J16") (pin "4") (pinfunction "4_4") (pintype "passive"))
      (node (ref "J16") (pin "5") (pinfunction "5_5") (pintype "passive"))
      (node (ref "J16") (pin "6") (pinfunction "6_6") (pintype "passive"))
      (node (ref "J16") (pin "7") (pinfunction "7_7") (pintype "passive"))
      (node (ref "J16") (pin "8") (pinfunction "8_8") (pintype "passive"))
      (node (ref "J17") (pin "3") (pinfunction "3_3") (pintype "passive"))
      (node (ref "J17") (pin "4") (pinfunction "4_4") (pintype "passive"))
      (node (ref "J17") (pin "5") (pinfunction "5_5") (pintype "passive"))
      (node (ref "J17") (pin "6") (pinfunction "6_6") (pintype "passive"))
      (node (ref "J17") (pin "7") (pinfunction "7_7") (pintype "passive"))
      (node (ref "J17") (pin "8") (pinfunction "8_8") (pintype "passive"))
      (node (ref "J18") (pin "3") (pinfunction "3_3") (pintype "passive"))
      (node (ref "J18") (pin "4") (pinfunction "4_4") (pintype "passive"))
      (node (ref "J18") (pin "5") (pinfunction "5_5") (pintype "passive"))
      (node (ref "J18") (pin "6") (pinfunction "6_6") (pintype "passive"))
      (node (ref "J18") (pin "7") (pinfunction "7_7") (pintype "passive"))
      (node (ref "J18") (pin "8") (pinfunction "8_8") (pintype "passive"))
      (node (ref "J19") (pin "3") (pinfunction "3_3") (pintype "passive"))
      (node (ref "J19") (pin "4") (pinfunction "4_4") (pintype "passive"))
      (node (ref "J19") (pin "5") (pinfunction "5_5") (pintype "passive"))
      (node (ref "J19") (pin "6") (pinfunction "6_6") (pintype "passive"))
      (node (ref "J19") (pin "7") (pinfunction "7_7") (pintype "passive"))
      (node (ref "J19") (pin "8") (pinfunction "8_8") (pintype "passive"))
      (node (ref "J2") (pin "3") (pinfunction "3_3") (pintype "passive"))
      (node (ref "J2") (pin "4") (pinfunction "4_4") (pintype "passive"))
      (node (ref "J2") (pin "5") (pinfunction "5_5") (pintype "passive"))
      (node (ref "J2") (pin "6") (pinfunction "6_6") (pintype "passive"))
      (node (ref "J2") (pin "7") (pinfunction "7_7") (pintype "passive"))
      (node (ref "J2") (pin "8") (pinfunction "8_8") (pintype "passive"))
      (node (ref "J20") (pin "3") (pinfunction "3_3") (pintype "passive"))
      (node (ref "J20") (pin "4") (pinfunction "4_4") (pintype "passive"))
      (node (ref "J20") (pin "5") (pinfunction "5_5") (pintype "passive"))
      (node (ref "J20") (pin "6") (pinfunction "6_6") (pintype "passive"))
      (node (ref "J20") (pin "7") (pinfunction "7_7") (pintype "passive"))
      (node (ref "J20") (pin "8") (pinfunction "8_8") (pintype "passive"))
      (node (ref "J21") (pin "3") (pinfunction "3_3") (pintype "passive"))
      (node (ref "J21") (pin "4") (pinfunction "4_4") (pintype "passive"))
      (node (ref "J21") (pin "5") (pinfunction "5_5") (pintype "passive"))
      (node (ref "J21") (pin "6") (pinfunction "6_6") (pintype "passive"))
      (node (ref "J21") (pin "7") (pinfunction "7_7") (pintype "passive"))
      (node (ref "J21") (pin "8") (pinfunction "8_8") (pintype "passive"))
      (node (ref "J22") (pin "3") (pinfunction "3_3") (pintype "passive"))
      (node (ref "J22") (pin "4") (pinfunction "4_4") (pintype "passive"))
      (node (ref "J22") (pin "5") (pinfunction "5_5") (pintype "passive"))
      (node (ref "J22") (pin "6") (pinfunction "6_6") (pintype "passive"))
      (node (ref "J22") (pin "7") (pinfunction "7_7") (pintype "passive"))
      (node (ref "J22") (pin "8") (pinfunction "8_8") (pintype "passive"))
      (node (ref "J23") (pin "3") (pinfunction "3_3") (pintype "passive"))
      (node (ref "J23") (pin "4") (pinfunction "4_4") (pintype "passive"))
      (node (ref "J23") (pin "5") (pinfunction "5_5") (pintype "passive"))
      (node (ref "J23") (pin "6") (pinfunction "6_6") (pintype "passive"))
      (node (ref "J23") (pin "7") (pinfunction "7_7") (pintype "passive"))
      (node (ref "J23") (pin "8") (pinfunction "8_8") (pintype "passive"))
      (node (ref "J24") (pin "3") (pinfunction "3_3") (pintype "passive"))
      (node (ref "J24") (pin "4") (pinfunction "4_4") (pintype "passive"))
      (node (ref "J24") (pin "5") (pinfunction "5_5") (pintype "passive"))
      (node (ref "J24") (pin "6") (pinfunction "6_6") (pintype "passive"))
      (node (ref "J24") (pin "7") (pinfunction "7_7") (pintype "passive"))
      (node (ref "J24") (pin "8") (pinfunction "8_8") (pintype "passive"))
      (node (ref "J25") (pin "3") (pinfunction "3_3") (pintype "passive"))
      (node (ref "J25") (pin "4") (pinfunction "4_4") (pintype "passive"))
      (node (ref "J25") (pin "5") (pinfunction "5_5") (pintype "passive"))
      (node (ref "J25") (pin "6") (pinfunction "6_6") (pintype "passive"))
      (node (ref "J25") (pin "7") (pinfunction "7_7") (pintype "passive"))
      (node (ref "J25") (pin "8") (pinfunction "8_8") (pintype "passive"))
      (node (ref "J26") (pin "3") (pinfunction "3_3") (pintype "passive"))
      (node (ref "J26") (pin "4") (pinfunction "4_4") (pintype "passive"))
      (node (ref "J26") (pin "5") (pinfunction "5_5") (pintype "passive"))
      (node (ref "J26") (pin "6") (pinfunction "6_6") (pintype "passive"))
      (node (ref "J26") (pin "7") (pinfunction "7_7") (pintype "passive"))
      (node (ref "J26") (pin "8") (pinfunction "8_8") (pintype "passive"))
      (node (ref "J27") (pin "3") (pinfunction "3_3") (pintype "passive"))
      (node (ref "J27") (pin "4") (pinfunction "4_4") (pintype "passive"))
      (node (ref "J27") (pin "5") (pinfunction "5_5") (pintype "passive"))
      (node (ref "J27") (pin "6") (pinfunction "6_6") (pintype "passive"))
      (node (ref "J27") (pin "7") (pinfunction "7_7") (pintype "passive"))
      (node (ref "J27") (pin "8") (pinfunction "8_8") (pintype "passive"))
      (node (ref "J28") (pin "3") (pinfunction "3_3") (pintype "passive"))
      (node (ref "J28") (pin "4") (pinfunction "4_4") (pintype "passive"))
      (node (ref "J28") (pin "5") (pinfunction "5_5") (pintype "passive"))
      (node (ref "J28") (pin "6") (pinfunction "6_6") (pintype "passive"))
      (node (ref "J28") (pin "7") (pinfunction "7_7") (pintype "passive"))
      (node (ref "J28") (pin "8") (pinfunction "8_8") (pintype "passive"))
      (node (ref "J29") (pin "3") (pinfunction "3_3") (pintype "passive"))
      (node (ref "J29") (pin "4") (pinfunction "4_4") (pintype "passive"))
      (node (ref "J29") (pin "5") (pinfunction "5_5") (pintype "passive"))
      (node (ref "J29") (pin "6") (pinfunction "6_6") (pintype "passive"))
      (node (ref "J29") (pin "7") (pinfunction "7_7") (pintype "passive"))
      (node (ref "J29") (pin "8") (pinfunction "8_8") (pintype "passive"))
      (node (ref "J3") (pin "3") (pinfunction "3_3") (pintype "bidirectional"))
      (node (ref "J3") (pin "4") (pinfunction "4_4") (pintype "bidirectional"))
      (node (ref "J30") (pin "3") (pinfunction "3_3") (pintype "passive"))
      (node (ref "J30") (pin "4") (pinfunction "4_4") (pintype "passive"))
      (node (ref "J30") (pin "5") (pinfunction "5_5") (pintype "passive"))
      (node (ref "J30") (pin "6") (pinfunction "6_6") (pintype "passive"))
      (node (ref "J30") (pin "7") (pinfunction "7_7") (pintype "passive"))
      (node (ref "J30") (pin "8") (pinfunction "8_8") (pintype "passive"))
      (node (ref "J31") (pin "3") (pinfunction "3_3") (pintype "passive"))
      (node (ref "J31") (pin "4") (pinfunction "4_4") (pintype "passive"))
      (node (ref "J31") (pin "5") (pinfunction "5_5") (pintype "passive"))
      (node (ref "J31") (pin "6") (pinfunction "6_6") (pintype "passive"))
      (node (ref "J31") (pin "7") (pinfunction "7_7") (pintype "passive"))
      (node (ref "J31") (pin "8") (pinfunction "8_8") (pintype "passive"))
      (node (ref "J32") (pin "3") (pinfunction "3_3") (pintype "passive"))
      (node (ref "J32") (pin "4") (pinfunction "4_4") (pintype "passive"))
      (node (ref "J32") (pin "5") (pinfunction "5_5") (pintype "passive"))
      (node (ref "J32") (pin "6") (pinfunction "6_6") (pintype "passive"))
      (node (ref "J32") (pin "7") (pinfunction "7_7") (pintype "passive"))
      (node (ref "J32") (pin "8") (pinfunction "8_8") (pintype "passive"))
      (node (ref "J33") (pin "3") (pinfunction "3_3") (pintype "passive"))
      (node (ref "J33") (pin "4") (pinfunction "4_4") (pintype "passive"))
      (node (ref "J33") (pin "5") (pinfunction "5_5") (pintype "passive"))
      (node (ref "J33") (pin "6") (pinfunction "6_6") (pintype "passive"))
      (node (ref "J33") (pin "7") (pinfunction "7_7") (pintype "passive"))
      (node (ref "J33") (pin "8") (pinfunction "8_8") (pintype "passive"))
      (node (ref "J34") (pin "3") (pinfunction "3_3") (pintype "passive"))
      (node (ref "J34") (pin "4") (pinfunction "4_4") (pintype "passive"))
      (node (ref "J34") (pin "5") (pinfunction "5_5") (pintype "passive"))
      (node (ref "J34") (pin "6") (pinfunction "6_6") (pintype "passive"))
      (node (ref "J34") (pin "7") (pinfunction "7_7") (pintype "passive"))
      (node (ref "J34") (pin "8") (pinfunction "8_8") (pintype "passive"))
      (node (ref "J4") (pin "3") (pinfunction "3_3") (pintype "bidirectional"))
      (node (ref "J4") (pin "4") (pinfunction "4_4") (pintype "bidirectional"))
      (node (ref "J5") (pin "1") (pinfunction "1_1") (pintype "bidirectional"))
      (node (ref "J5") (pin "2") (pinfunction "2_2") (pintype "bidirectional"))
      (node (ref "J5") (pin "3") (pinfunction "3_3") (pintype "bidirectional"))
      (node (ref "J5") (pin "4") (pinfunction "4_4") (pintype "bidirectional"))
      (node (ref "J5") (pin "5") (pinfunction "5_5") (pintype "bidirectional"))
      (node (ref "J5") (pin "6") (pinfunction "6_6") (pintype "bidirectional"))
      (node (ref "J6") (pin "3") (pinfunction "3_3") (pintype "passive"))
      (node (ref "J6") (pin "4") (pinfunction "4_4") (pintype "passive"))
      (node (ref "J6") (pin "5") (pinfunction "5_5") (pintype "passive"))
      (node (ref "J6") (pin "6") (pinfunction "6_6") (pintype "passive"))
      (node (ref "J6") (pin "7") (pinfunction "7_7") (pintype "passive"))
      (node (ref "J6") (pin "8") (pinfunction "8_8") (pintype "passive"))
      (node (ref "J7") (pin "3") (pinfunction "3_3") (pintype "passive"))
      (node (ref "J7") (pin "4") (pinfunction "4_4") (pintype "passive"))
      (node (ref "J7") (pin "5") (pinfunction "5_5") (pintype "passive"))
      (node (ref "J7") (pin "6") (pinfunction "6_6") (pintype "passive"))
      (node (ref "J7") (pin "7") (pinfunction "7_7") (pintype "passive"))
      (node (ref "J7") (pin "8") (pinfunction "8_8") (pintype "passive"))
      (node (ref "J8") (pin "3") (pinfunction "3_3") (pintype "passive"))
      (node (ref "J8") (pin "4") (pinfunction "4_4") (pintype "passive"))
      (node (ref "J8") (pin "5") (pinfunction "5_5") (pintype "passive"))
      (node (ref "J8") (pin "6") (pinfunction "6_6") (pintype "passive"))
      (node (ref "J8") (pin "7") (pinfunction "7_7") (pintype "passive"))
      (node (ref "J8") (pin "8") (pinfunction "8_8") (pintype "passive"))
      (node (ref "J9") (pin "3") (pinfunction "3_3") (pintype "passive"))
      (node (ref "J9") (pin "4") (pinfunction "4_4") (pintype "passive"))
      (node (ref "J9") (pin "5") (pinfunction "5_5") (pintype "passive"))
      (node (ref "J9") (pin "6") (pinfunction "6_6") (pintype "passive"))
      (node (ref "J9") (pin "7") (pinfunction "7_7") (pintype "passive"))
      (node (ref "J9") (pin "8") (pinfunction "8_8") (pintype "passive"))
      (node (ref "U$1") (pin "P$1") (pinfunction "P$1_P$1") (pintype "bidirectional"))
      (node (ref "U$10") (pin "P$1") (pinfunction "P$1_P$1") (pintype "bidirectional"))
      (node (ref "U$11") (pin "P$1") (pinfunction "P$1_P$1") (pintype "bidirectional"))
      (node (ref "U$12") (pin "P$1") (pinfunction "P$1_P$1") (pintype "bidirectional"))
      (node (ref "U$2") (pin "P$1") (pinfunction "P$1_P$1") (pintype "bidirectional"))
      (node (ref "U$3") (pin "P$1") (pinfunction "P$1_P$1") (pintype "bidirectional"))
      (node (ref "U$4") (pin "P$1") (pinfunction "P$1_P$1") (pintype "bidirectional"))
      (node (ref "U$5") (pin "P$1") (pinfunction "P$1_P$1") (pintype "bidirectional"))
      (node (ref "U$6") (pin "P$1") (pinfunction "P$1_P$1") (pintype "bidirectional"))
      (node (ref "U$8") (pin "P$1") (pinfunction "P$1_P$1") (pintype "bidirectional"))
      (node (ref "U$9") (pin "P$1") (pinfunction "P$1_P$1") (pintype "bidirectional"))
    )
    (net (code "10") (name "VCC{slash}2") (class "Default")
      (node (ref "J1") (pin "10") (pinfunction "10_10") (pintype "passive"))
      (node (ref "J1") (pin "9") (pinfunction "9_9") (pintype "passive"))
      (node (ref "J2") (pin "10") (pinfunction "10_10") (pintype "passive"))
      (node (ref "J2") (pin "9") (pinfunction "9_9") (pintype "passive"))
      (node (ref "J25") (pin "10") (pinfunction "10_10") (pintype "passive"))
      (node (ref "J25") (pin "9") (pinfunction "9_9") (pintype "passive"))
      (node (ref "J26") (pin "10") (pinfunction "10_10") (pintype "passive"))
      (node (ref "J26") (pin "9") (pinfunction "9_9") (pintype "passive"))
      (node (ref "J27") (pin "10") (pinfunction "10_10") (pintype "passive"))
      (node (ref "J27") (pin "9") (pinfunction "9_9") (pintype "passive"))
      (node (ref "J28") (pin "10") (pinfunction "10_10") (pintype "passive"))
      (node (ref "J28") (pin "9") (pinfunction "9_9") (pintype "passive"))
      (node (ref "J29") (pin "10") (pinfunction "10_10") (pintype "passive"))
      (node (ref "J29") (pin "9") (pinfunction "9_9") (pintype "passive"))
      (node (ref "J30") (pin "10") (pinfunction "10_10") (pintype "passive"))
      (node (ref "J30") (pin "9") (pinfunction "9_9") (pintype "passive"))
      (node (ref "J31") (pin "10") (pinfunction "10_10") (pintype "passive"))
      (node (ref "J31") (pin "9") (pinfunction "9_9") (pintype "passive"))
      (node (ref "J32") (pin "10") (pinfunction "10_10") (pintype "passive"))
      (node (ref "J32") (pin "9") (pinfunction "9_9") (pintype "passive"))
      (node (ref "J33") (pin "10") (pinfunction "10_10") (pintype "passive"))
      (node (ref "J33") (pin "9") (pinfunction "9_9") (pintype "passive"))
      (node (ref "J34") (pin "10") (pinfunction "10_10") (pintype "passive"))
      (node (ref "J34") (pin "9") (pinfunction "9_9") (pintype "passive"))
      (node (ref "J4") (pin "5") (pinfunction "5_5") (pintype "bidirectional"))
      (node (ref "J4") (pin "6") (pinfunction "6_6") (pintype "bidirectional"))
      (node (ref "J6") (pin "10") (pinfunction "10_10") (pintype "passive"))
      (node (ref "J6") (pin "9") (pinfunction "9_9") (pintype "passive"))
      (node (ref "J7") (pin "10") (pinfunction "10_10") (pintype "passive"))
      (node (ref "J7") (pin "9") (pinfunction "9_9") (pintype "passive"))
      (node (ref "J8") (pin "10") (pinfunction "10_10") (pintype "passive"))
      (node (ref "J8") (pin "9") (pinfunction "9_9") (pintype "passive"))
    )
  )
)
